# Ampli2.net
KiCad netlist of a schematic drawn in Altium Designer
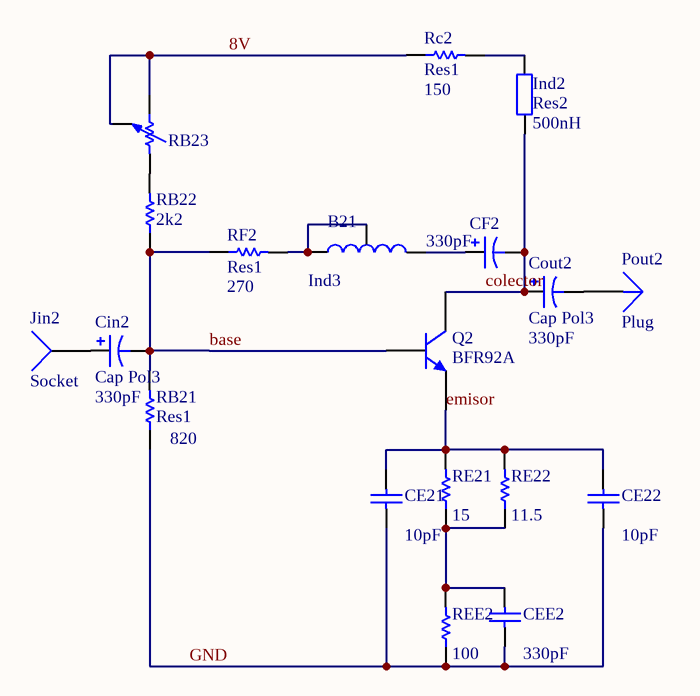
[diagram p0: Ampli2.SchDoc]

(export (version "E")
  (design (tool "Eeschema 10.0.6"))
  (components
    (comp (ref "B21") (value "Ind3") (footprint "Ind 7mm") (libsource (lib "epf") (part "Ind3")))
    (comp (ref "CE21")
      (value "10pF")
      (footprint "1608[0603]")
      (description "Capacitor (Semiconductor SIM Model)")
      (fields (field (name "Comment") "Cap Semi") (field (name "PUBLISHER") "Altium Limited"))
      (libsource (lib "Miscellaneous Devices") (part "Cap Semi"))
    )
    (comp (ref "CE22")
      (value "10pF")
      (footprint "1608[0603]")
      (description "Capacitor (Semiconductor SIM Model)")
      (fields (field (name "Comment") "Cap Semi") (field (name "PUBLISHER") "Altium Limited"))
      (libsource (lib "Miscellaneous Devices") (part "Cap Semi"))
    )
    (comp (ref "CEE2")
      (value "330pF")
      (footprint "1608[0603]")
      (description "Capacitor (Semiconductor SIM Model)")
      (fields (field (name "Comment") "Cap Semi") (field (name "PUBLISHER") "Altium Limited"))
      (libsource (lib "Miscellaneous Devices") (part "Cap Semi"))
    )
    (comp (ref "CF2")
      (value "330pF")
      (footprint "C0805")
      (description "Polarized Capacitor (Surface Mount)")
      (fields (field (name "Comment") "Cap Pol3") (field (name "PUBLISHER") "Altium Limited"))
      (libsource (lib "Miscellaneous Devices") (part "Cap Pol3"))
    )
    (comp (ref "Cin2")
      (value "Cap Pol3")
      (footprint "C0805")
      (description "Polarized Capacitor (Surface Mount)")
      (fields (field (name "ALTIUM_VALUE") "330pF") (field (name "PUBLISHER") "Altium Limited"))
      (libsource (lib "Miscellaneous Devices") (part "Cap Pol3"))
    )
    (comp (ref "Cout2")
      (value "Cap Pol3")
      (footprint "C0805")
      (description "Polarized Capacitor (Surface Mount)")
      (fields (field (name "ALTIUM_VALUE") "330pF") (field (name "PUBLISHER") "Altium Limited"))
      (libsource (lib "Miscellaneous Devices") (part "Cap Pol3"))
    )
    (comp (ref "Ind2")
      (value "Res2")
      (footprint "AXIAL-0.4")
      (description "Resistor")
      (fields (field (name "ALTIUM_VALUE") "500nH") (field (name "PUBLISHER") "Altium Limited"))
      (libsource (lib "Miscellaneous Devices") (part "Res2"))
    )
    (comp (ref "Jin2")
      (value "Socket")
      (footprint "PIN1")
      (fields (field (name "PUBLISHER") "Altium Limited"))
      (libsource (lib "Miscellaneous Connectors") (part "Socket"))
    )
    (comp (ref "Pout2")
      (value "Plug")
      (footprint "PIN1")
      (fields (field (name "PUBLISHER") "Altium Limited"))
      (libsource (lib "Miscellaneous Connectors") (part "Plug"))
    )
    (comp (ref "Q2")
      (value "BFR92A")
      (footprint "SOT23")
      (description "NPN 5 GHz Wideband Transistor")
      (fields (field (name "PUBLISHER") "Altium Limited"))
      (libsource (lib "Philips Discrete BJT - RF Transistor") (part "BFR92A"))
    )
    (comp (ref "RB21")
      (value "Res1")
      (footprint "AXIAL-0.3")
      (description "Resistor")
      (fields (field (name "ALTIUM_VALUE") "820") (field (name "PUBLISHER") "Altium Limited"))
      (libsource (lib "Miscellaneous Devices") (part "Res1"))
    )
    (comp (ref "RB22")
      (value "2k2")
      (footprint "AXIAL-0.3")
      (description "Resistor")
      (fields (field (name "Comment") "Res1") (field (name "PUBLISHER") "Altium Limited"))
      (libsource (lib "Miscellaneous Devices") (part "Res1"))
    )
    (comp (ref "RB23") (value "Pot") (footprint "Potenciometro") (libsource (lib "epf") (part "Pot")))
    (comp (ref "Rc2")
      (value "Res1")
      (footprint "AXIAL-0.3")
      (description "Resistor")
      (fields (field (name "ALTIUM_VALUE") "150") (field (name "PUBLISHER") "Altium Limited"))
      (libsource (lib "Miscellaneous Devices") (part "Res1"))
    )
    (comp (ref "RE21")
      (value "15")
      (footprint "1608[0603]")
      (description "Semiconductor Resistor")
      (fields (field (name "Comment") "Res Semi") (field (name "PUBLISHER") "Altium Limited"))
      (libsource (lib "Miscellaneous Devices") (part "Res Semi"))
    )
    (comp (ref "RE22")
      (value "11.5")
      (footprint "2012[0805]")
      (description "Semiconductor Resistor")
      (fields (field (name "Comment") "Res Semi") (field (name "PUBLISHER") "Altium Limited"))
      (libsource (lib "Miscellaneous Devices") (part "Res Semi"))
    )
    (comp (ref "REE2")
      (value "100")
      (footprint "2012[0805]")
      (description "Semiconductor Resistor")
      (fields (field (name "Comment") "Res Semi") (field (name "PUBLISHER") "Altium Limited"))
      (libsource (lib "Miscellaneous Devices") (part "Res Semi"))
    )
    (comp (ref "RF2")
      (value "Res1")
      (footprint "AXIAL-0.3")
      (description "Resistor")
      (fields (field (name "ALTIUM_VALUE") "270") (field (name "PUBLISHER") "Altium Limited"))
      (libsource (lib "Miscellaneous Devices") (part "Res1"))
    )
  )
  (nets
    (net (code "1") (name "/8V") (class "Default")
      (node (ref "RB23") (pin "2") (pinfunction "2_2") (pintype "passive"))
      (node (ref "RB23") (pin "3") (pinfunction "3_3") (pintype "passive"))
      (node (ref "Rc2") (pin "1") (pinfunction "1_1") (pintype "passive"))
    )
    (net (code "2") (name "/GND") (class "Default")
      (node (ref "CE21") (pin "1") (pinfunction "1_1") (pintype "passive"))
      (node (ref "CE22") (pin "1") (pinfunction "1_1") (pintype "passive"))
      (node (ref "CEE2") (pin "1") (pinfunction "1_1") (pintype "passive"))
      (node (ref "RB21") (pin "1") (pinfunction "1_1") (pintype "passive"))
      (node (ref "REE2") (pin "1") (pinfunction "1_1") (pintype "passive"))
    )
    (net (code "3") (name "/base") (class "Default")
      (node (ref "Cin2") (pin "2") (pinfunction "2_2") (pintype "passive"))
      (node (ref "Q2") (pin "1") (pinfunction "B_1") (pintype "passive"))
      (node (ref "RB21") (pin "2") (pinfunction "2_2") (pintype "passive"))
      (node (ref "RB22") (pin "1") (pinfunction "1_1") (pintype "passive"))
      (node (ref "RF2") (pin "1") (pinfunction "1_1") (pintype "passive"))
    )
    (net (code "4") (name "/colector") (class "Default")
      (node (ref "CF2") (pin "2") (pinfunction "2_2") (pintype "passive"))
      (node (ref "Cout2") (pin "1") (pinfunction "1_1") (pintype "passive"))
      (node (ref "Ind2") (pin "1") (pinfunction "1_1") (pintype "passive"))
      (node (ref "Q2") (pin "3") (pinfunction "C_3") (pintype "passive"))
    )
    (net (code "5") (name "/emisor") (class "Default")
      (node (ref "CE21") (pin "2") (pinfunction "2_2") (pintype "passive"))
      (node (ref "CE22") (pin "2") (pinfunction "2_2") (pintype "passive"))
      (node (ref "Q2") (pin "2") (pinfunction "E_2") (pintype "passive"))
      (node (ref "RE21") (pin "2") (pinfunction "2_2") (pintype "passive"))
      (node (ref "RE22") (pin "2") (pinfunction "2_2") (pintype "passive"))
    )
    (net (code "6") (name "Net-(B21-Pad0)") (class "Default")
      (node (ref "B21") (pin "0") (pinfunction "0_0") (pintype "passive"))
      (node (ref "B21") (pin "2") (pinfunction "2_2") (pintype "passive"))
      (node (ref "RF2") (pin "2") (pinfunction "2_2") (pintype "passive"))
    )
    (net (code "7") (name "Net-(B21-Pad1)") (class "Default")
      (node (ref "B21") (pin "1") (pinfunction "1_1") (pintype "passive"))
      (node (ref "CF2") (pin "1") (pinfunction "1_1") (pintype "passive"))
    )
    (net (code "8") (name "Net-(CEE2-Pad2)") (class "Default")
      (node (ref "CEE2") (pin "2") (pinfunction "2_2") (pintype "passive"))
      (node (ref "RE21") (pin "1") (pinfunction "1_1") (pintype "passive"))
      (node (ref "RE22") (pin "1") (pinfunction "1_1") (pintype "passive"))
      (node (ref "REE2") (pin "2") (pinfunction "2_2") (pintype "passive"))
    )
    (net (code "9") (name "Net-(Cin2-Pad1)") (class "Default")
      (node (ref "Cin2") (pin "1") (pinfunction "1_1") (pintype "passive"))
      (node (ref "Jin2") (pin "1") (pinfunction "1_1") (pintype "passive"))
    )
    (net (code "10") (name "Net-(Cout2-Pad2)") (class "Default")
      (node (ref "Cout2") (pin "2") (pinfunction "2_2") (pintype "passive"))
      (node (ref "Pout2") (pin "1") (pinfunction "1_1") (pintype "passive"))
    )
    (net (code "11") (name "Net-(Ind2-Pad2)") (class "Default")
      (node (ref "Ind2") (pin "2") (pinfunction "2_2") (pintype "passive"))
      (node (ref "Rc2") (pin "2") (pinfunction "2_2") (pintype "passive"))
    )
    (net (code "12") (name "Net-(RB22-Pad2)") (class "Default")
      (node (ref "RB22") (pin "2") (pinfunction "2_2") (pintype "passive"))
      (node (ref "RB23") (pin "1") (pinfunction "1_1") (pintype "passive"))
    )
  )
)
